# MINI_FOC.net
KiCad netlist of a schematic drawn in EasyEDA Pro
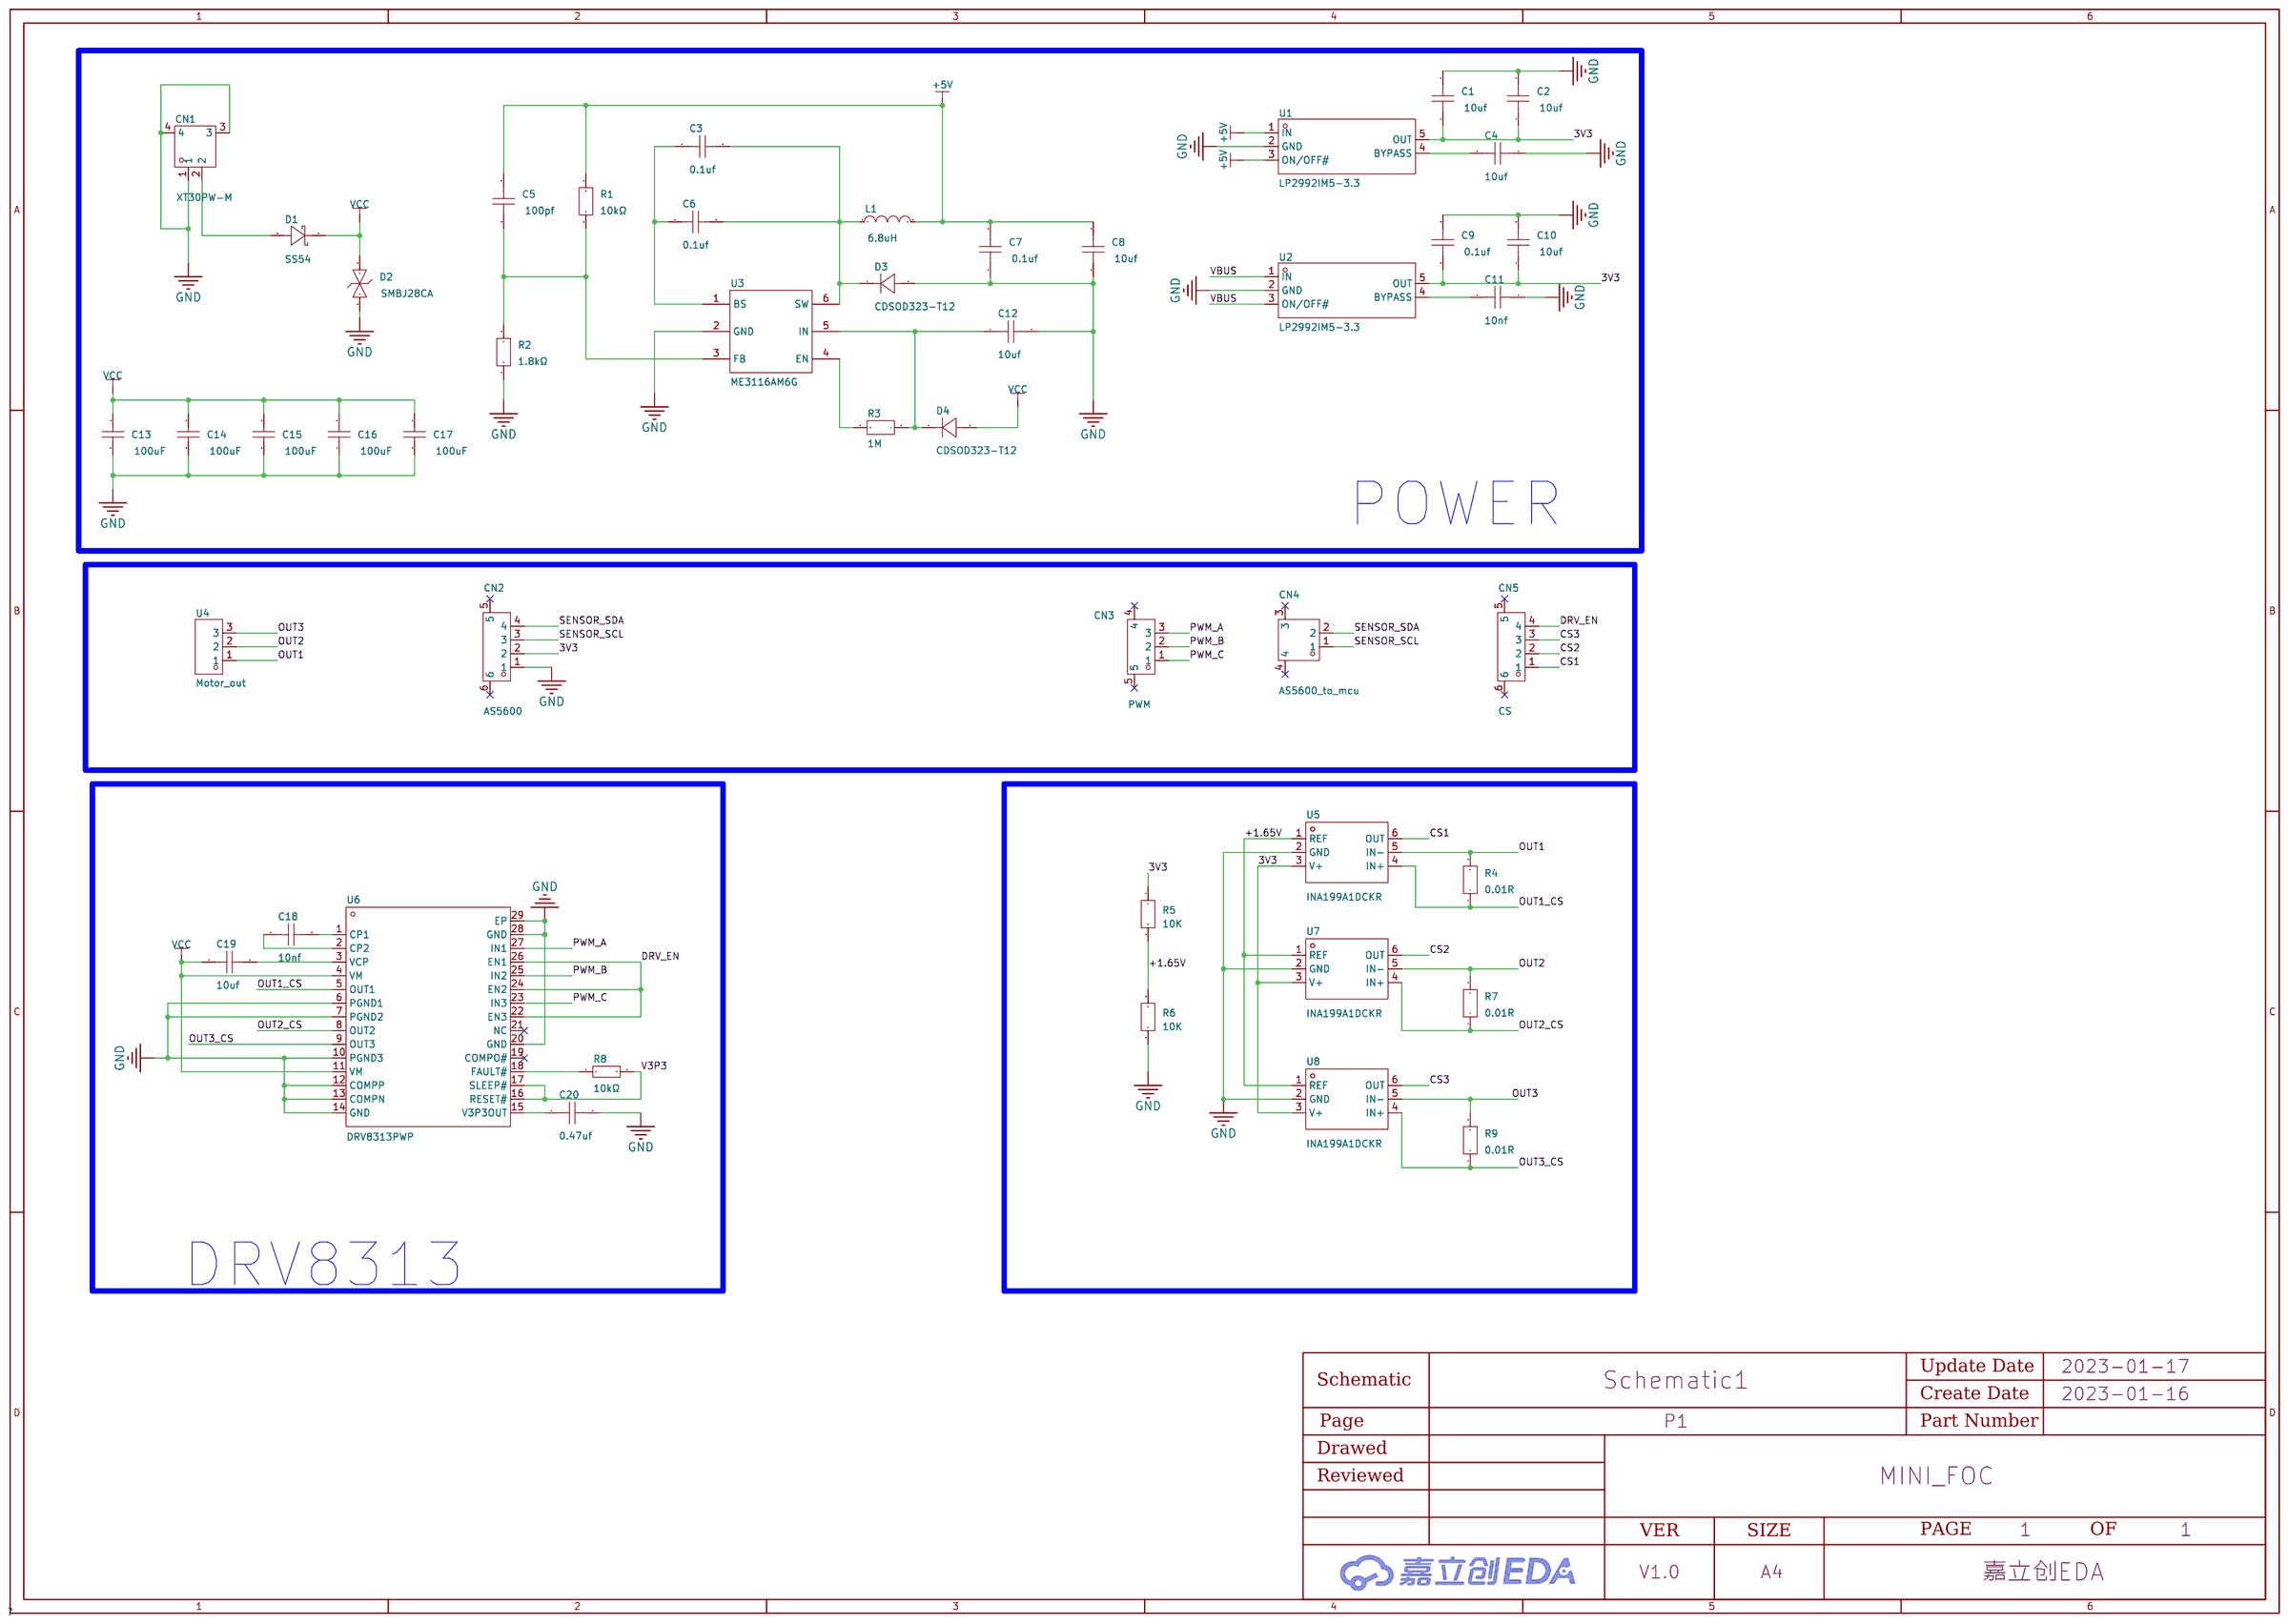
[diagram p0: schematic sheet]

(export (version "E")
  (design (tool "Eeschema 10.0.6"))
  (components
    (comp (ref "C1")
      (value "10uf")
      (footprint "easyedapro:C0603")
      (description "容值:100nF;精度:±10%;额定电压:50V;材质(温度系数):X7R;")
      (fields
        (field (name "Manufacturer Part") "CL10B104KB8NNNC")
        (field (name "Manufacturer") "SAMSUNG(三星)")
      )
      (libsource (lib "easyedapro") (part "CL10B104KB8NNNC"))
    )
    (comp (ref "C2")
      (value "10uf")
      (footprint "easyedapro:C0603")
      (description "容值:100nF;精度:±10%;额定电压:50V;材质(温度系数):X7R;")
      (fields
        (field (name "Manufacturer Part") "CL10B104KB8NNNC")
        (field (name "Manufacturer") "SAMSUNG(三星)")
      )
      (libsource (lib "easyedapro") (part "CL10B104KB8NNNC"))
    )
    (comp (ref "C3")
      (value "0.1uf")
      (footprint "easyedapro:C0603")
      (description "容值:100nF;精度:±10%;额定电压:50V;材质(温度系数):X7R;")
      (fields
        (field (name "Manufacturer Part") "CL10B104KB8NNNC")
        (field (name "Manufacturer") "SAMSUNG(三星)")
      )
      (libsource (lib "easyedapro") (part "CL10B104KB8NNNC"))
    )
    (comp (ref "C4")
      (value "10uf")
      (footprint "easyedapro:C0603")
      (description "容值:100nF;精度:±10%;额定电压:50V;材质(温度系数):X7R;")
      (fields
        (field (name "Manufacturer Part") "CL10B104KB8NNNC")
        (field (name "Manufacturer") "SAMSUNG(三星)")
      )
      (libsource (lib "easyedapro") (part "CL10B104KB8NNNC"))
    )
    (comp (ref "C5")
      (value "100pf")
      (footprint "easyedapro:C0603")
      (description "容值:100nF;精度:±10%;额定电压:50V;材质(温度系数):X7R;")
      (fields
        (field (name "Manufacturer Part") "CL10B104KB8NNNC")
        (field (name "Manufacturer") "SAMSUNG(三星)")
      )
      (libsource (lib "easyedapro") (part "CL10B104KB8NNNC"))
    )
    (comp (ref "C6")
      (value "0.1uf")
      (footprint "easyedapro:C0603")
      (description "容值:100nF;精度:±10%;额定电压:50V;材质(温度系数):X7R;")
      (fields
        (field (name "Manufacturer Part") "CL10B104KB8NNNC")
        (field (name "Manufacturer") "SAMSUNG(三星)")
      )
      (libsource (lib "easyedapro") (part "CL10B104KB8NNNC"))
    )
    (comp (ref "C7")
      (value "0.1uf")
      (footprint "easyedapro:C0603")
      (description "容值:100nF;精度:±10%;额定电压:50V;材质(温度系数):X7R;")
      (fields
        (field (name "Manufacturer Part") "CL10B104KB8NNNC")
        (field (name "Manufacturer") "SAMSUNG(三星)")
      )
      (libsource (lib "easyedapro") (part "CL10B104KB8NNNC"))
    )
    (comp (ref "C8")
      (value "10uf")
      (footprint "easyedapro:C0603")
      (description "容值:100nF;精度:±10%;额定电压:50V;材质(温度系数):X7R;")
      (fields
        (field (name "Manufacturer Part") "CL10B104KB8NNNC")
        (field (name "Manufacturer") "SAMSUNG(三星)")
      )
      (libsource (lib "easyedapro") (part "CL10B104KB8NNNC"))
    )
    (comp (ref "C9")
      (value "0.1uf")
      (footprint "easyedapro:C0603")
      (description "容值:100nF;精度:±10%;额定电压:50V;材质(温度系数):X7R;")
      (fields
        (field (name "Manufacturer Part") "CL10B104KB8NNNC")
        (field (name "Manufacturer") "SAMSUNG(三星)")
      )
      (libsource (lib "easyedapro") (part "CL10B104KB8NNNC"))
    )
    (comp (ref "C10")
      (value "10uf")
      (footprint "easyedapro:C0603")
      (description "容值:100nF;精度:±10%;额定电压:50V;材质(温度系数):X7R;")
      (fields
        (field (name "Manufacturer Part") "CL10B104KB8NNNC")
        (field (name "Manufacturer") "SAMSUNG(三星)")
      )
      (libsource (lib "easyedapro") (part "CL10B104KB8NNNC"))
    )
    (comp (ref "C11")
      (value "10nf")
      (footprint "easyedapro:C0603")
      (description "容值:100nF;精度:±10%;额定电压:50V;材质(温度系数):X7R;")
      (fields
        (field (name "Manufacturer Part") "CL10B104KB8NNNC")
        (field (name "Manufacturer") "SAMSUNG(三星)")
      )
      (libsource (lib "easyedapro") (part "CL10B104KB8NNNC"))
    )
    (comp (ref "C12")
      (value "10uf")
      (footprint "easyedapro:C0603")
      (description "容值:100nF;精度:±10%;额定电压:50V;材质(温度系数):X7R;")
      (fields
        (field (name "Manufacturer Part") "CL10B104KB8NNNC")
        (field (name "Manufacturer") "SAMSUNG(三星)")
      )
      (libsource (lib "easyedapro") (part "CL10B104KB8NNNC"))
    )
    (comp (ref "C13")
      (value "100uF")
      (footprint "easyedapro:C1206")
      (description "容值:100uF;精度:±20%;额定电压:6.3V;材质(温度系数):X5R;")
      (fields
        (field (name "Manufacturer Part") "CL31A107MQHNNNE")
        (field (name "Manufacturer") "SAMSUNG(三星)")
      )
      (libsource (lib "easyedapro") (part "CL31A107MQHNNNE"))
    )
    (comp (ref "C14")
      (value "100uF")
      (footprint "easyedapro:C1206")
      (description "容值:100uF;精度:±20%;额定电压:6.3V;材质(温度系数):X5R;")
      (fields
        (field (name "Manufacturer Part") "CL31A107MQHNNNE")
        (field (name "Manufacturer") "SAMSUNG(三星)")
      )
      (libsource (lib "easyedapro") (part "CL31A107MQHNNNE"))
    )
    (comp (ref "C15")
      (value "100uF")
      (footprint "easyedapro:C1206")
      (description "容值:100uF;精度:±20%;额定电压:6.3V;材质(温度系数):X5R;")
      (fields
        (field (name "Manufacturer Part") "CL31A107MQHNNNE")
        (field (name "Manufacturer") "SAMSUNG(三星)")
      )
      (libsource (lib "easyedapro") (part "CL31A107MQHNNNE"))
    )
    (comp (ref "C16")
      (value "100uF")
      (footprint "easyedapro:C1206")
      (description "容值:100uF;精度:±20%;额定电压:6.3V;材质(温度系数):X5R;")
      (fields
        (field (name "Manufacturer Part") "CL31A107MQHNNNE")
        (field (name "Manufacturer") "SAMSUNG(三星)")
      )
      (libsource (lib "easyedapro") (part "CL31A107MQHNNNE"))
    )
    (comp (ref "C17")
      (value "100uF")
      (footprint "easyedapro:C1206")
      (description "容值:100uF;精度:±20%;额定电压:6.3V;材质(温度系数):X5R;")
      (fields
        (field (name "Manufacturer Part") "CL31A107MQHNNNE")
        (field (name "Manufacturer") "SAMSUNG(三星)")
      )
      (libsource (lib "easyedapro") (part "CL31A107MQHNNNE"))
    )
    (comp (ref "C18")
      (value "10nf")
      (footprint "easyedapro:C0603")
      (description "容值:100nF;精度:±10%;额定电压:50V;材质(温度系数):X7R;")
      (fields
        (field (name "Manufacturer Part") "CL10B104KB8NNNC")
        (field (name "Manufacturer") "SAMSUNG(三星)")
      )
      (libsource (lib "easyedapro") (part "CL10B104KB8NNNC"))
    )
    (comp (ref "C19")
      (value "10uf")
      (footprint "easyedapro:C0603")
      (description "容值:100nF;精度:±10%;额定电压:50V;材质(温度系数):X7R;")
      (fields
        (field (name "Manufacturer Part") "CL10B104KB8NNNC")
        (field (name "Manufacturer") "SAMSUNG(三星)")
      )
      (libsource (lib "easyedapro") (part "CL10B104KB8NNNC"))
    )
    (comp (ref "C20")
      (value "0.47uf")
      (footprint "easyedapro:C0603")
      (description "容值:100nF;精度:±10%;额定电压:50V;材质(温度系数):X7R;")
      (fields
        (field (name "Manufacturer Part") "CL10B104KB8NNNC")
        (field (name "Manufacturer") "SAMSUNG(三星)")
      )
      (libsource (lib "easyedapro") (part "CL10B104KB8NNNC"))
    )
    (comp (ref "CN1")
      (value "XT30PW-M")
      (footprint "easyedapro:CONN-TH_XT30PW-M")
      (description "Socket,DCsupply,XT30,male,PIN:2")
      (fields (field (name "Manufacturer") "AMASS(艾迈斯)"))
      (libsource (lib "easyedapro") (part "XT30PW-M"))
    )
    (comp (ref "CN2")
      (value "AS5600")
      (footprint "easyedapro:CONN-SMD_4P-P1.00_HDGC_HDGC1002WR-S-4P")
      (description "SH1.0针座卧贴 4P")
      (fields (field (name "Manufacturer Part") "HDGC1002WR-S-4P") (field (name "Manufacturer") "HDGC(华德共创)"))
      (libsource (lib "easyedapro") (part "HDGC1002WR-S-4P"))
    )
    (comp (ref "CN3")
      (value "PWM")
      (footprint "easyedapro:CONN-SMD_3P-P1.00_HDGC_1.0K-BH-3PWB")
      (description "1.0间距卧式贴片针座 3P")
      (fields (field (name "Manufacturer Part") "1.0K-BH-3PWB") (field (name "Manufacturer") "HDGC(华德共创)"))
      (libsource (lib "easyedapro") (part "1.0K-BH-3PWB"))
    )
    (comp (ref "CN4")
      (value "AS5600_to_mcu")
      (footprint "easyedapro:CONN-SMD_2P-P1.00_HDGC_1.0K-BH-2PWB")
      (description "1.0间距卧式贴片针座 2P")
      (fields (field (name "Manufacturer Part") "1.0K-BH-2PWB") (field (name "Manufacturer") "HDGC(华德共创)"))
      (libsource (lib "easyedapro") (part "1.0K-BH-2PWB"))
    )
    (comp (ref "CN5")
      (value "CS")
      (footprint "easyedapro:CONN-SMD_4P-P1.00_HDGC_HDGC1002WR-S-4P")
      (description "SH1.0针座卧贴 4P")
      (fields (field (name "Manufacturer Part") "HDGC1002WR-S-4P") (field (name "Manufacturer") "HDGC(华德共创)"))
      (libsource (lib "easyedapro") (part "HDGC1002WR-S-4P"))
    )
    (comp (ref "D1")
      (value "SS54")
      (footprint "easyedapro:DO-214AC_L4.3-W2.7-LS5.2-RD")
      (description "二极管配置:-;直流反向耐压(Vr):40V;平均整流电流(Io):5A;正向压降(Vf):550mV@5A;反向电流(Ir):500uA@40V;")
      (fields (field (name "Manufacturer") "KUU"))
      (libsource (lib "easyedapro") (part "SS54_C2891720"))
    )
    (comp (ref "D2")
      (value "SMBJ28CA")
      (footprint "easyedapro:SMB_L4.6-W3.6-LS5.3-BI")
      (description "极性:双向;")
      (fields (field (name "Manufacturer") "TWGMC(台湾迪嘉)"))
      (libsource (lib "easyedapro") (part "SMBJ28CA_C726872"))
    )
    (comp (ref "D3")
      (value "CDSOD323-T12")
      (footprint "easyedapro:SOD-323_L1.8-W1.3-LS2.5-RD")
      (fields (field (name "Manufacturer") "BOURNS"))
      (libsource (lib "easyedapro") (part "CDSOD323-T12"))
    )
    (comp (ref "D4")
      (value "CDSOD323-T12")
      (footprint "easyedapro:SOD-323_L1.8-W1.3-LS2.5-RD")
      (fields (field (name "Manufacturer") "BOURNS"))
      (libsource (lib "easyedapro") (part "CDSOD323-T12"))
    )
    (comp (ref "L1")
      (value "6.8uH")
      (footprint "easyedapro:IND-SMD_L2.0-W1.6")
      (description "精度:±20%;直流电阻(DCR):86mΩ;电感值:1.5uH;额定电流:1.7A;")
      (fields
        (field (name "Manufacturer Part") "HPI201612-1R5M")
        (field (name "Manufacturer") "3L COILS(三礼)")
      )
      (libsource (lib "easyedapro") (part "HPI201612-1R5M"))
    )
    (comp (ref "R1")
      (value "10kΩ")
      (footprint "easyedapro:R0603")
      (fields (field (name "Manufacturer Part") "ERA3ARB472V") (field (name "Manufacturer") "PANASONIC(松下)"))
      (libsource (lib "easyedapro") (part "ERA3ARB472V"))
    )
    (comp (ref "R2")
      (value "1.8kΩ")
      (footprint "easyedapro:R0603")
      (fields
        (field (name "Manufacturer Part") "ERA3ARB472V")
        (field (name "Manufacturer") "PANASONIC(松下)")
        (field (name "Tolerance") "±0.1%")
      )
      (libsource (lib "easyedapro") (part "ERA3ARB472V"))
    )
    (comp (ref "R3")
      (value "1M")
      (footprint "easyedapro:R0603")
      (fields
        (field (name "Manufacturer Part") "ERA3ARB472V")
        (field (name "Manufacturer") "PANASONIC(松下)")
        (field (name "Tolerance") "±0.1%")
      )
      (libsource (lib "easyedapro") (part "ERA3ARB472V"))
    )
    (comp (ref "R4")
      (value "0.01R")
      (footprint "easyedapro:R0805")
      (fields
        (field (name "Manufacturer Part") "ERA6ARB104V")
        (field (name "Manufacturer") "PANASONIC(松下)")
        (field (name "Tolerance") "±0.1%")
      )
      (libsource (lib "easyedapro") (part "ERA6ARB104V"))
    )
    (comp (ref "R5")
      (value "10K")
      (footprint "easyedapro:R0603")
      (fields
        (field (name "Manufacturer Part") "ERA3ARB472V")
        (field (name "Manufacturer") "PANASONIC(松下)")
        (field (name "Tolerance") "±0.1%")
      )
      (libsource (lib "easyedapro") (part "ERA3ARB472V"))
    )
    (comp (ref "R6")
      (value "10K")
      (footprint "easyedapro:R0603")
      (fields
        (field (name "Manufacturer Part") "ERA3ARB472V")
        (field (name "Manufacturer") "PANASONIC(松下)")
        (field (name "Tolerance") "±0.1%")
      )
      (libsource (lib "easyedapro") (part "ERA3ARB472V"))
    )
    (comp (ref "R7")
      (value "0.01R")
      (footprint "easyedapro:R0805")
      (fields (field (name "Manufacturer Part") "ERA6ARB104V") (field (name "Manufacturer") "PANASONIC(松下)"))
      (libsource (lib "easyedapro") (part "ERA6ARB104V"))
    )
    (comp (ref "R8")
      (value "10kΩ")
      (footprint "easyedapro:R0402")
      (description "电阻类型:薄膜电阻;阻值:1kΩ;精度:±0.1%;功率:63mW;温度系数:±25ppm/K;最大工作电压:50V;工作温度范围:-55°C~+155°C;")
      (fields (field (name "Manufacturer Part") "ERA2AEB102X") (field (name "Manufacturer") "PANASONIC(松下)"))
      (libsource (lib "easyedapro") (part "ERA2AEB102X"))
    )
    (comp (ref "R9")
      (value "0.01R")
      (footprint "easyedapro:R0805")
      (fields (field (name "Manufacturer Part") "ERA6ARB104V") (field (name "Manufacturer") "PANASONIC(松下)"))
      (libsource (lib "easyedapro") (part "ERA6ARB104V"))
    )
    (comp (ref "U1")
      (value "LP2992IM5-3.3")
      (footprint "easyedapro:SOT-23-5_L2.9-W1.6-P0.95-LS2.8-BL")
      (fields (field (name "Manufacturer") "TI(德州仪器)"))
      (libsource (lib "easyedapro") (part "LP2992IM5-3.3"))
    )
    (comp (ref "U2")
      (value "LP2992IM5-3.3")
      (footprint "easyedapro:SOT-23-5_L2.9-W1.6-P0.95-LS2.8-BL")
      (fields (field (name "Manufacturer") "TI(德州仪器)"))
      (libsource (lib "easyedapro") (part "LP2992IM5-3.3"))
    )
    (comp (ref "U3")
      (value "ME3116AM6G")
      (footprint "easyedapro:SOT-23-6_L2.9-W1.6-P0.95-LS2.8-BR")
      (description "功能类型:降压型;同步整流:-;输出通道数:-;拓扑结构:-;输入电压:-;输出电流(最大值):-;开关频率:-;")
      (fields (field (name "Manufacturer") "MICRONE(南京微盟)"))
      (libsource (lib "easyedapro") (part "ME3116"))
    )
    (comp (ref "U4")
      (value "Motor_out")
      (footprint "easyedapro:CONN-TH_MR30-M")
      (description "模型锂电连接器（两件套） 三芯")
      (fields (field (name "Manufacturer Part") "MR30-M") (field (name "Manufacturer") "AMASS(艾迈斯)"))
      (libsource (lib "easyedapro") (part "MR30-M"))
    )
    (comp (ref "U5")
      (value "INA199A1DCKR")
      (footprint "easyedapro:SC-70-6_L2.2-W1.3-P0.65-LS2.1-BR")
      (description "工作电压:2.7V~26V;工作电压:2.7V~26V;监控类型:Low/High Side;增益Max(V/V):50;共模输入电压:-0.3V~26V;共模输入电压:-0.3V~26V;")
      (fields (field (name "Manufacturer") "TI(德州仪器)"))
      (libsource (lib "easyedapro") (part "INA199A1DCKR"))
    )
    (comp (ref "U6")
      (value "DRV8313PWP")
      (footprint "easyedapro:HTSSOP-28_L9.8-W4.5-P0.65-LS6.6-BL-EP")
      (description "最大电压为 65V 的 3A 峰值三相电机驱动器 28-HTSSOP -40 to 125")
      (fields (field (name "Manufacturer") "TI(德州仪器)"))
      (libsource (lib "easyedapro") (part "DRV8313PWP"))
    )
    (comp (ref "U7")
      (value "INA199A1DCKR")
      (footprint "easyedapro:SC-70-6_L2.2-W1.3-P0.65-LS2.1-BR")
      (description "工作电压:2.7V~26V;工作电压:2.7V~26V;监控类型:Low/High Side;增益Max(V/V):50;共模输入电压:-0.3V~26V;共模输入电压:-0.3V~26V;")
      (fields (field (name "Manufacturer") "TI(德州仪器)"))
      (libsource (lib "easyedapro") (part "INA199A1DCKR"))
    )
    (comp (ref "U8")
      (value "INA199A1DCKR")
      (footprint "easyedapro:SC-70-6_L2.2-W1.3-P0.65-LS2.1-BR")
      (description "工作电压:2.7V~26V;工作电压:2.7V~26V;监控类型:Low/High Side;增益Max(V/V):50;共模输入电压:-0.3V~26V;共模输入电压:-0.3V~26V;")
      (fields (field (name "Manufacturer") "TI(德州仪器)"))
      (libsource (lib "easyedapro") (part "INA199A1DCKR"))
    )
  )
  (nets
    (net (code "1") (name "+5V") (class "Default")
      (node (ref "C5") (pin "2") (pinfunction "2_2") (pintype "input"))
      (node (ref "C7") (pin "2") (pinfunction "2_2") (pintype "input"))
      (node (ref "C8") (pin "2") (pinfunction "2_2") (pintype "input"))
      (node (ref "L1") (pin "2") (pinfunction "2_2") (pintype "input"))
      (node (ref "R1") (pin "2") (pinfunction "2_2") (pintype "input"))
      (node (ref "U1") (pin "1") (pinfunction "IN_1") (pintype "input"))
      (node (ref "U1") (pin "3") (pinfunction "ON/OFF#_3") (pintype "input"))
    )
    (net (code "2") (name "/+1.65V") (class "Default")
      (node (ref "R5") (pin "2") (pinfunction "2_2") (pintype "input"))
      (node (ref "R6") (pin "1") (pinfunction "1_1") (pintype "input"))
      (node (ref "U5") (pin "1") (pinfunction "REF_1") (pintype "input"))
      (node (ref "U7") (pin "1") (pinfunction "REF_1") (pintype "input"))
      (node (ref "U8") (pin "1") (pinfunction "REF_1") (pintype "input"))
    )
    (net (code "3") (name "/3V3") (class "Default")
      (node (ref "C1") (pin "1") (pinfunction "1_1") (pintype "input"))
      (node (ref "C10") (pin "1") (pinfunction "1_1") (pintype "input"))
      (node (ref "C2") (pin "1") (pinfunction "1_1") (pintype "input"))
      (node (ref "C9") (pin "1") (pinfunction "1_1") (pintype "input"))
      (node (ref "CN2") (pin "2") (pinfunction "2_2") (pintype "input"))
      (node (ref "R5") (pin "1") (pinfunction "1_1") (pintype "input"))
      (node (ref "U1") (pin "5") (pinfunction "OUT_5") (pintype "input"))
      (node (ref "U2") (pin "5") (pinfunction "OUT_5") (pintype "input"))
      (node (ref "U5") (pin "3") (pinfunction "V+_3") (pintype "input"))
      (node (ref "U7") (pin "3") (pinfunction "V+_3") (pintype "input"))
      (node (ref "U8") (pin "3") (pinfunction "V+_3") (pintype "input"))
    )
    (net (code "4") (name "/CS1") (class "Default")
      (node (ref "CN5") (pin "1") (pinfunction "1_1") (pintype "input"))
      (node (ref "U5") (pin "6") (pinfunction "OUT_6") (pintype "input"))
    )
    (net (code "5") (name "/CS2") (class "Default")
      (node (ref "CN5") (pin "2") (pinfunction "2_2") (pintype "input"))
      (node (ref "U7") (pin "6") (pinfunction "OUT_6") (pintype "input"))
    )
    (net (code "6") (name "/CS3") (class "Default")
      (node (ref "CN5") (pin "3") (pinfunction "3_3") (pintype "input"))
      (node (ref "U8") (pin "6") (pinfunction "OUT_6") (pintype "input"))
    )
    (net (code "7") (name "/DRV_EN") (class "Default")
      (node (ref "CN5") (pin "4") (pinfunction "4_4") (pintype "input"))
      (node (ref "U6") (pin "22") (pinfunction "EN3_22") (pintype "input"))
      (node (ref "U6") (pin "24") (pinfunction "EN2_24") (pintype "input"))
      (node (ref "U6") (pin "26") (pinfunction "EN1_26") (pintype "input"))
    )
    (net (code "8") (name "/OUT1") (class "Default")
      (node (ref "R4") (pin "2") (pinfunction "2_2") (pintype "input"))
      (node (ref "U4") (pin "1") (pinfunction "1_1") (pintype "input"))
      (node (ref "U5") (pin "5") (pinfunction "IN-_5") (pintype "input"))
    )
    (net (code "9") (name "/OUT1_CS") (class "Default")
      (node (ref "R4") (pin "1") (pinfunction "1_1") (pintype "input"))
      (node (ref "U5") (pin "4") (pinfunction "IN+_4") (pintype "input"))
      (node (ref "U6") (pin "5") (pinfunction "OUT1_5") (pintype "input"))
    )
    (net (code "10") (name "/OUT2") (class "Default")
      (node (ref "R7") (pin "2") (pinfunction "2_2") (pintype "input"))
      (node (ref "U4") (pin "2") (pinfunction "2_2") (pintype "input"))
      (node (ref "U7") (pin "5") (pinfunction "IN-_5") (pintype "input"))
    )
    (net (code "11") (name "/OUT2_CS") (class "Default")
      (node (ref "R7") (pin "1") (pinfunction "1_1") (pintype "input"))
      (node (ref "U6") (pin "8") (pinfunction "OUT2_8") (pintype "input"))
      (node (ref "U7") (pin "4") (pinfunction "IN+_4") (pintype "input"))
    )
    (net (code "12") (name "/OUT3") (class "Default")
      (node (ref "R9") (pin "2") (pinfunction "2_2") (pintype "input"))
      (node (ref "U4") (pin "3") (pinfunction "3_3") (pintype "input"))
      (node (ref "U8") (pin "5") (pinfunction "IN-_5") (pintype "input"))
    )
    (net (code "13") (name "/OUT3_CS") (class "Default")
      (node (ref "R9") (pin "1") (pinfunction "1_1") (pintype "input"))
      (node (ref "U6") (pin "9") (pinfunction "OUT3_9") (pintype "input"))
      (node (ref "U8") (pin "4") (pinfunction "IN+_4") (pintype "input"))
    )
    (net (code "14") (name "/PWM_A") (class "Default")
      (node (ref "CN3") (pin "3") (pinfunction "3_3") (pintype "input"))
      (node (ref "U6") (pin "27") (pinfunction "IN1_27") (pintype "input"))
    )
    (net (code "15") (name "/PWM_B") (class "Default")
      (node (ref "CN3") (pin "2") (pinfunction "2_2") (pintype "input"))
      (node (ref "U6") (pin "25") (pinfunction "IN2_25") (pintype "input"))
    )
    (net (code "16") (name "/PWM_C") (class "Default")
      (node (ref "CN3") (pin "1") (pinfunction "1_1") (pintype "input"))
      (node (ref "U6") (pin "23") (pinfunction "IN3_23") (pintype "input"))
    )
    (net (code "17") (name "/SENSOR_SCL") (class "Default")
      (node (ref "CN2") (pin "3") (pinfunction "3_3") (pintype "input"))
      (node (ref "CN4") (pin "1") (pinfunction "1_1") (pintype "input"))
    )
    (net (code "18") (name "/SENSOR_SDA") (class "Default")
      (node (ref "CN2") (pin "4") (pinfunction "4_4") (pintype "input"))
      (node (ref "CN4") (pin "2") (pinfunction "2_2") (pintype "input"))
    )
    (net (code "19") (name "/V3P3") (class "Default")
      (node (ref "R8") (pin "2") (pinfunction "2_2") (pintype "input"))
      (node (ref "U6") (pin "16") (pinfunction "RESET#_16") (pintype "input"))
      (node (ref "U6") (pin "17") (pinfunction "SLEEP#_17") (pintype "input"))
    )
    (net (code "20") (name "/VBUS") (class "Default")
      (node (ref "U2") (pin "1") (pinfunction "IN_1") (pintype "input"))
      (node (ref "U2") (pin "3") (pinfunction "ON/OFF#_3") (pintype "input"))
    )
    (net (code "21") (name "GND") (class "Default")
      (node (ref "C1") (pin "2") (pinfunction "2_2") (pintype "input"))
      (node (ref "C10") (pin "2") (pinfunction "2_2") (pintype "input"))
      (node (ref "C11") (pin "1") (pinfunction "1_1") (pintype "input"))
      (node (ref "C12") (pin "2") (pinfunction "2_2") (pintype "input"))
      (node (ref "C13") (pin "1") (pinfunction "1_1") (pintype "input"))
      (node (ref "C14") (pin "1") (pinfunction "1_1") (pintype "input"))
      (node (ref "C15") (pin "1") (pinfunction "1_1") (pintype "input"))
      (node (ref "C16") (pin "1") (pinfunction "1_1") (pintype "input"))
      (node (ref "C17") (pin "1") (pinfunction "1_1") (pintype "input"))
      (node (ref "C2") (pin "2") (pinfunction "2_2") (pintype "input"))
      (node (ref "C20") (pin "2") (pinfunction "2_2") (pintype "input"))
      (node (ref "C4") (pin "1") (pinfunction "1_1") (pintype "input"))
      (node (ref "C7") (pin "1") (pinfunction "1_1") (pintype "input"))
      (node (ref "C8") (pin "1") (pinfunction "1_1") (pintype "input"))
      (node (ref "C9") (pin "2") (pinfunction "2_2") (pintype "input"))
      (node (ref "CN1") (pin "1") (pinfunction "1_1") (pintype "input"))
      (node (ref "CN1") (pin "3") (pinfunction "3_3") (pintype "input"))
      (node (ref "CN1") (pin "4") (pinfunction "4_4") (pintype "input"))
      (node (ref "CN2") (pin "1") (pinfunction "1_1") (pintype "input"))
      (node (ref "D2") (pin "2") (pinfunction "2_2") (pintype "input"))
      (node (ref "D3") (pin "2") (pinfunction "A_2") (pintype "input"))
      (node (ref "R2") (pin "1") (pinfunction "1_1") (pintype "input"))
      (node (ref "R6") (pin "2") (pinfunction "2_2") (pintype "input"))
      (node (ref "U1") (pin "2") (pinfunction "GND_2") (pintype "input"))
      (node (ref "U2") (pin "2") (pinfunction "GND_2") (pintype "input"))
      (node (ref "U3") (pin "2") (pinfunction "GND_2") (pintype "input"))
      (node (ref "U5") (pin "2") (pinfunction "GND_2") (pintype "input"))
      (node (ref "U6") (pin "10") (pinfunction "PGND3_10") (pintype "input"))
      (node (ref "U6") (pin "12") (pinfunction "COMPP_12") (pintype "input"))
      (node (ref "U6") (pin "13") (pinfunction "COMPN_13") (pintype "input"))
      (node (ref "U6") (pin "14") (pinfunction "GND_14") (pintype "input"))
      (node (ref "U6") (pin "20") (pinfunction "GND_20") (pintype "input"))
      (node (ref "U6") (pin "28") (pinfunction "GND_28") (pintype "input"))
      (node (ref "U6") (pin "29") (pinfunction "EP_29") (pintype "input"))
      (node (ref "U6") (pin "6") (pinfunction "PGND1_6") (pintype "input"))
      (node (ref "U6") (pin "7") (pinfunction "PGND2_7") (pintype "input"))
      (node (ref "U7") (pin "2") (pinfunction "GND_2") (pintype "input"))
      (node (ref "U8") (pin "2") (pinfunction "GND_2") (pintype "input"))
    )
    (net (code "22") (name "Net-(D1-A)") (class "Default")
      (node (ref "CN1") (pin "2") (pinfunction "2_2") (pintype "input"))
      (node (ref "D1") (pin "2") (pinfunction "A_2") (pintype "input"))
    )
    (net (code "23") (name "Net-(D3-K)") (class "Default")
      (node (ref "C3") (pin "2") (pinfunction "2_2") (pintype "input"))
      (node (ref "C6") (pin "2") (pinfunction "2_2") (pintype "input"))
      (node (ref "D3") (pin "1") (pinfunction "K_1") (pintype "input"))
      (node (ref "L1") (pin "1") (pinfunction "1_1") (pintype "input"))
      (node (ref "U3") (pin "6") (pinfunction "SW_6") (pintype "input"))
    )
    (net (code "24") (name "Net-(D4-K)") (class "Default")
      (node (ref "C12") (pin "1") (pinfunction "1_1") (pintype "input"))
      (node (ref "D4") (pin "1") (pinfunction "K_1") (pintype "input"))
      (node (ref "R3") (pin "1") (pinfunction "1_1") (pintype "input"))
      (node (ref "U3") (pin "5") (pinfunction "IN_5") (pintype "input"))
    )
    (net (code "25") (name "Net-(U1-BYPASS)") (class "Default")
      (node (ref "C4") (pin "2") (pinfunction "2_2") (pintype "input"))
      (node (ref "U1") (pin "4") (pinfunction "BYPASS_4") (pintype "input"))
    )
    (net (code "26") (name "Net-(U2-BYPASS)") (class "Default")
      (node (ref "C11") (pin "2") (pinfunction "2_2") (pintype "input"))
      (node (ref "U2") (pin "4") (pinfunction "BYPASS_4") (pintype "input"))
    )
    (net (code "27") (name "Net-(U3-BS)") (class "Default")
      (node (ref "C3") (pin "1") (pinfunction "1_1") (pintype "input"))
      (node (ref "C6") (pin "1") (pinfunction "1_1") (pintype "input"))
      (node (ref "U3") (pin "1") (pinfunction "BS_1") (pintype "input"))
    )
    (net (code "28") (name "Net-(U3-EN)") (class "Default")
      (node (ref "R3") (pin "2") (pinfunction "2_2") (pintype "input"))
      (node (ref "U3") (pin "4") (pinfunction "EN_4") (pintype "input"))
    )
    (net (code "29") (name "Net-(U3-FB)") (class "Default")
      (node (ref "C5") (pin "1") (pinfunction "1_1") (pintype "input"))
      (node (ref "R1") (pin "1") (pinfunction "1_1") (pintype "input"))
      (node (ref "R2") (pin "2") (pinfunction "2_2") (pintype "input"))
      (node (ref "U3") (pin "3") (pinfunction "FB_3") (pintype "input"))
    )
    (net (code "30") (name "Net-(U6-CP1)") (class "Default")
      (node (ref "C18") (pin "2") (pinfunction "2_2") (pintype "input"))
      (node (ref "U6") (pin "1") (pinfunction "CP1_1") (pintype "input"))
    )
    (net (code "31") (name "Net-(U6-CP2)") (class "Default")
      (node (ref "C18") (pin "1") (pinfunction "1_1") (pintype "input"))
      (node (ref "U6") (pin "2") (pinfunction "CP2_2") (pintype "input"))
    )
    (net (code "32") (name "Net-(U6-FAULT#)") (class "Default")
      (node (ref "R8") (pin "1") (pinfunction "1_1") (pintype "input"))
      (node (ref "U6") (pin "18") (pinfunction "FAULT#_18") (pintype "input"))
    )
    (net (code "33") (name "Net-(U6-V3P3OUT)") (class "Default")
      (node (ref "C20") (pin "1") (pinfunction "1_1") (pintype "input"))
      (node (ref "U6") (pin "15") (pinfunction "V3P3OUT_15") (pintype "input"))
    )
    (net (code "34") (name "Net-(U6-VCP)") (class "Default")
      (node (ref "C19") (pin "2") (pinfunction "2_2") (pintype "input"))
      (node (ref "U6") (pin "3") (pinfunction "VCP_3") (pintype "input"))
    )
    (net (code "35") (name "VCC") (class "Default")
      (node (ref "C13") (pin "2") (pinfunction "2_2") (pintype "input"))
      (node (ref "C14") (pin "2") (pinfunction "2_2") (pintype "input"))
      (node (ref "C15") (pin "2") (pinfunction "2_2") (pintype "input"))
      (node (ref "C16") (pin "2") (pinfunction "2_2") (pintype "input"))
      (node (ref "C17") (pin "2") (pinfunction "2_2") (pintype "input"))
      (node (ref "C19") (pin "1") (pinfunction "1_1") (pintype "input"))
      (node (ref "D1") (pin "1") (pinfunction "K_1") (pintype "input"))
      (node (ref "D2") (pin "1") (pinfunction "1_1") (pintype "input"))
      (node (ref "D4") (pin "2") (pinfunction "A_2") (pintype "input"))
      (node (ref "U6") (pin "11") (pinfunction "VM_11") (pintype "input"))
      (node (ref "U6") (pin "4") (pinfunction "VM_4") (pintype "input"))
    )
    (net (code "36") (name "unconnected-(CN2-Pad5)") (class "Default")
      (node (ref "CN2") (pin "5") (pinfunction "5_5") (pintype "input+no_connect"))
    )
    (net (code "37") (name "unconnected-(CN2-Pad6)") (class "Default")
      (node (ref "CN2") (pin "6") (pinfunction "6_6") (pintype "input+no_connect"))
    )
    (net (code "38") (name "unconnected-(CN3-Pad4)") (class "Default")
      (node (ref "CN3") (pin "4") (pinfunction "4_4") (pintype "input+no_connect"))
    )
    (net (code "39") (name "unconnected-(CN3-Pad5)") (class "Default")
      (node (ref "CN3") (pin "5") (pinfunction "5_5") (pintype "input+no_connect"))
    )
    (net (code "40") (name "unconnected-(CN4-Pad3)") (class "Default")
      (node (ref "CN4") (pin "3") (pinfunction "3_3") (pintype "input+no_connect"))
    )
    (net (code "41") (name "unconnected-(CN4-Pad4)") (class "Default")
      (node (ref "CN4") (pin "4") (pinfunction "4_4") (pintype "input+no_connect"))
    )
    (net (code "42") (name "unconnected-(CN5-Pad5)") (class "Default")
      (node (ref "CN5") (pin "5") (pinfunction "5_5") (pintype "input+no_connect"))
    )
    (net (code "43") (name "unconnected-(CN5-Pad6)") (class "Default")
      (node (ref "CN5") (pin "6") (pinfunction "6_6") (pintype "input+no_connect"))
    )
    (net (code "44") (name "unconnected-(U6-COMPO#-Pad19)") (class "Default")
      (node (ref "U6") (pin "19") (pinfunction "COMPO#_19") (pintype "input+no_connect"))
    )
    (net (code "45") (name "unconnected-(U6-NC-Pad21)") (class "Default")
      (node (ref "U6") (pin "21") (pinfunction "NC_21") (pintype "input+no_connect"))
    )
  )
)
